# MCH_FPGA_Banks_64_65_HR.net
KiCad netlist of a schematic drawn in Altium Designer
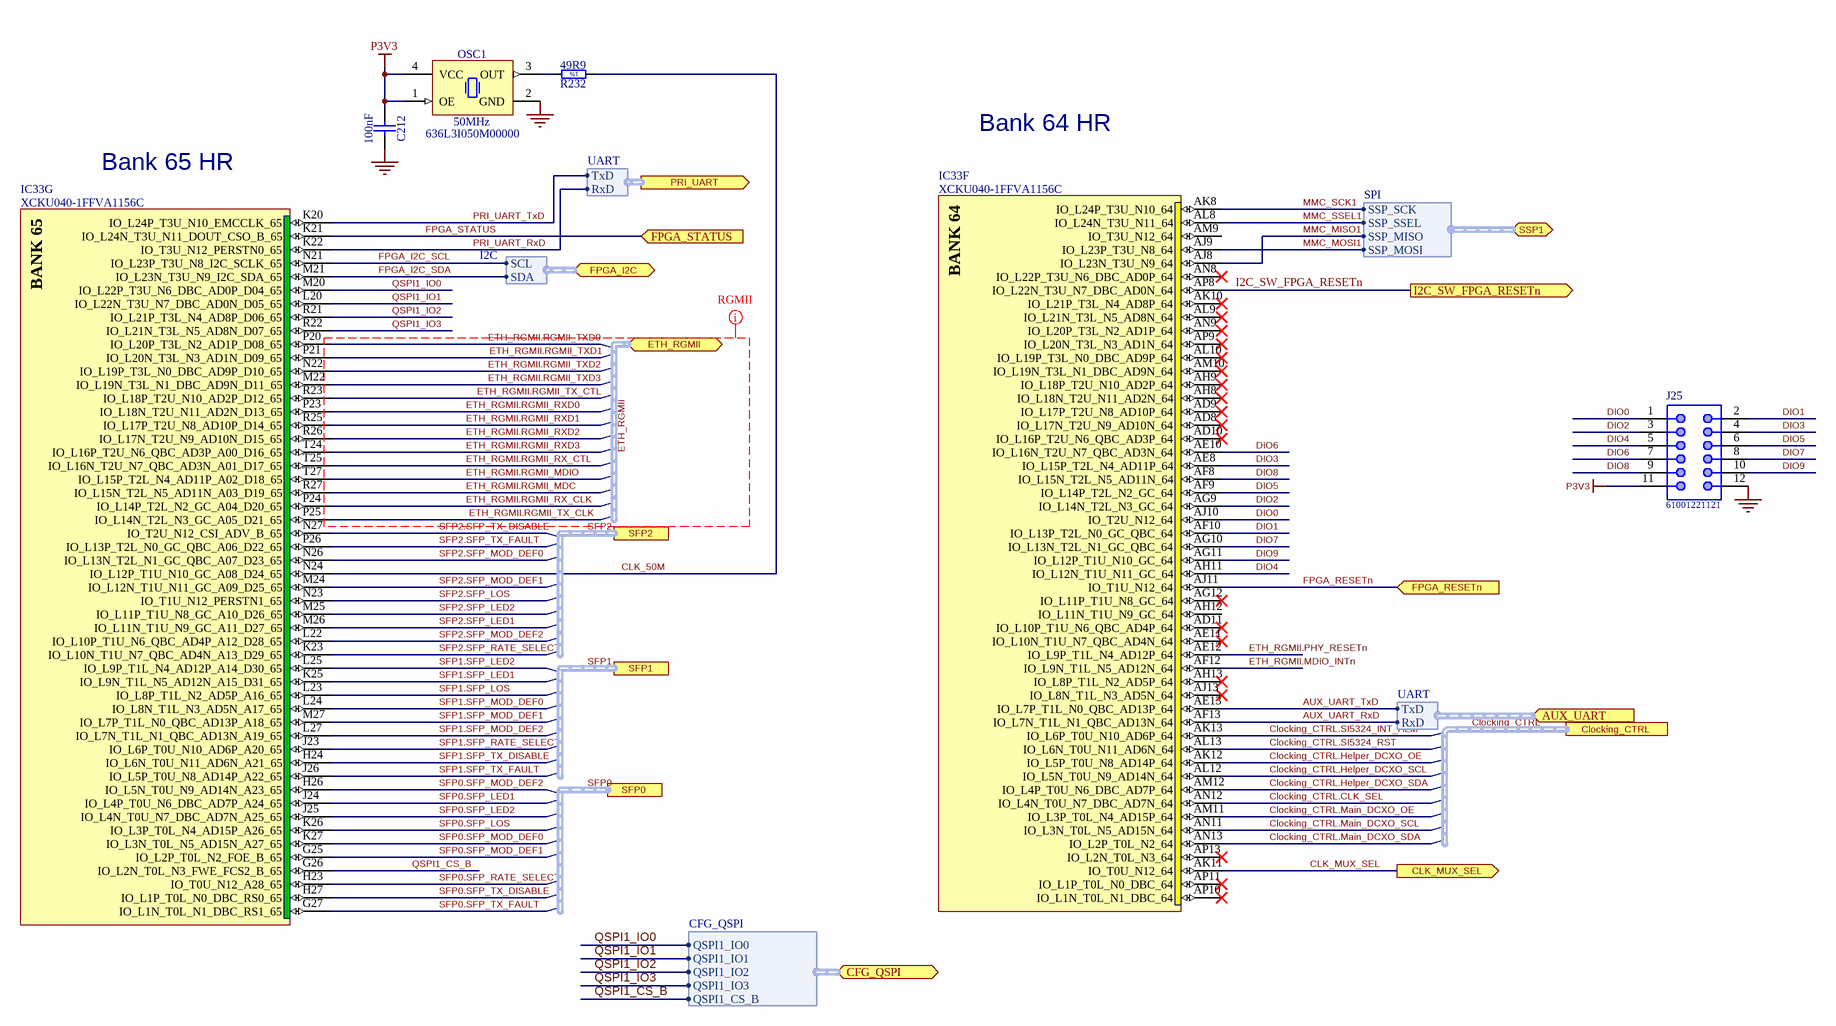
[diagram p0: MCH_FPGA_Banks_64_65_HR.SchDoc]

(export (version "E")
  (design (tool "Eeschema 10.0.6"))
  (components
    (comp (ref "C212")
      (value "100nF")
      (footprint "CAPC0603X33N")
      (description "Non-polarised capacitor")
      (fields
        (field (name "MANUFACTURER PART NUMBER") "CC0201_100NF_6.3V_10%_X5R")
        (field (name "MANUFACTURER") "GENERIC")
        (field (name "AUTHOR") "CERN DEM JLC")
      )
      (libsource (lib "Capacitors") (part "Capacitor - non polarized"))
    )
    (comp (ref "IC33")
      (value "XCKU040-1FFVA1156C")
      (footprint "BGA1156C100P34X34_3500X3500X350")
      (description "Kintex UltraScale FPGA, 520 I/O, 530K Cells, 1156-Ball BGA, Speed Grade 1, Commercial Grade")
      (fields (field (name "MANUFACTURER") "XILINX") (field (name "AUTHOR") "CERN DEM CA"))
      (libsource (lib "ICs And Semiconductors") (part "XCKU040-1FFVA1156C"))
    )
    (comp (ref "J25")
      (value "61001221121")
      (footprint "61001221121")
      (description "WR-PHD Pin Header, SMT, pitch 2.54mm, Dual Row, Vertical, 12p")
      (fields (field (name "MANUFACTURER") "Wurth Elektronik"))
      (libsource (lib "Altium_WR-PHD (rev20a)") (part "61001221121"))
    )
    (comp (ref "OSC1")
      (value "50MHz")
      (footprint "OSCSC254P320X500X130-4N")
      (description "Oscillator 4 pins 1=OE 2=GND 3=OUT 4=VCC")
      (fields
        (field (name "MANUFACTURER PART NUMBER") "636L3I050M00000")
        (field (name "MANUFACTURER") "CTS ELECTRONIC COMPONENTS")
        (field (name "PART NUMBER") "OSC_50MHZ_CTS_636L3I050M00000")
        (field (name "AUTHOR") "CERN DEM JMW")
      )
      (libsource (lib "ICs And Semiconductors") (part "Oscillator 1OE 2GND 3OUT 4VCC"))
    )
    (comp (ref "R232")
      (value "49R9")
      (footprint "RESC1005X40N")
      (description "Resistor - 1%")
      (fields
        (field (name "MANUFACTURER PART NUMBER") "R0402_49R9_1%_0.0625W_100PPM")
        (field (name "MANUFACTURER") "GENERIC")
        (field (name "AUTHOR") "CERN DEM JLC")
      )
      (libsource (lib "Resistors") (part "Resistor - 1%"))
    )
  )
  (nets
    (net (code "10") (name "/AUX_UART_RxD") (class "Default")
      (node (ref "IC33") (pin "AF13") (pinfunction "IO_L7N_T1L_N1_QBC_AD13N_64_AF13") (pintype "bidirectional"))
    )
    (net (code "11") (name "/AUX_UART_TxD") (class "Default")
      (node (ref "IC33") (pin "AE13") (pinfunction "IO_L7P_T1L_N0_QBC_AD13P_64_AE13") (pintype "bidirectional"))
    )
    (net (code "12") (name "/CLK_50M") (class "Default")
      (node (ref "IC33") (pin "N24") (pinfunction "IO_L12P_T1U_N10_GC_A08_D24_65_N24") (pintype "bidirectional"))
      (node (ref "R232") (pin "1") (pinfunction "1_1") (pintype "passive"))
    )
    (net (code "13") (name "/CLK_MUX_SEL") (class "Default")
      (node (ref "IC33") (pin "AK11") (pinfunction "IO_T0U_N12_64_AK11") (pintype "bidirectional"))
    )
    (net (code "14") (name "/Clocking_CTRL.CLK_SEL") (class "Default")
      (node (ref "IC33") (pin "AN12") (pinfunction "IO_L4N_T0U_N7_DBC_AD7N_64_AN12") (pintype "bidirectional"))
    )
    (net (code "15") (name "/Clocking_CTRL.Helper_DCXO_OE") (class "Default")
      (node (ref "IC33") (pin "AK12") (pinfunction "IO_L5P_T0U_N8_AD14P_64_AK12") (pintype "bidirectional"))
    )
    (net (code "16") (name "/Clocking_CTRL.Helper_DCXO_SCL") (class "Default")
      (node (ref "IC33") (pin "AL12") (pinfunction "IO_L5N_T0U_N9_AD14N_64_AL12") (pintype "bidirectional"))
    )
    (net (code "17") (name "/Clocking_CTRL.Helper_DCXO_SDA") (class "Default")
      (node (ref "IC33") (pin "AM12") (pinfunction "IO_L4P_T0U_N6_DBC_AD7P_64_AM12") (pintype "bidirectional"))
    )
    (net (code "18") (name "/Clocking_CTRL.Main_DCXO_OE") (class "Default")
      (node (ref "IC33") (pin "AM11") (pinfunction "IO_L3P_T0L_N4_AD15P_64_AM11") (pintype "bidirectional"))
    )
    (net (code "19") (name "/Clocking_CTRL.Main_DCXO_SCL") (class "Default")
      (node (ref "IC33") (pin "AN11") (pinfunction "IO_L3N_T0L_N5_AD15N_64_AN11") (pintype "bidirectional"))
    )
    (net (code "20") (name "/Clocking_CTRL.Main_DCXO_SDA") (class "Default")
      (node (ref "IC33") (pin "AN13") (pinfunction "IO_L2P_T0L_N2_64_AN13") (pintype "bidirectional"))
    )
    (net (code "21") (name "/Clocking_CTRL.SI5324_INT_ALM") (class "Default")
      (node (ref "IC33") (pin "AK13") (pinfunction "IO_L6P_T0U_N10_AD6P_64_AK13") (pintype "bidirectional"))
    )
    (net (code "22") (name "/Clocking_CTRL.SI5324_RST") (class "Default")
      (node (ref "IC33") (pin "AL13") (pinfunction "IO_L6N_T0U_N11_AD6N_64_AL13") (pintype "bidirectional"))
    )
    (net (code "23") (name "/DIO0") (class "Default")
      (node (ref "IC33") (pin "AJ10") (pinfunction "IO_T2U_N12_64_AJ10") (pintype "bidirectional"))
      (node (ref "J25") (pin "1") (pinfunction "1_1") (pintype "passive"))
    )
    (net (code "24") (name "/DIO1") (class "Default")
      (node (ref "IC33") (pin "AF10") (pinfunction "IO_L13P_T2L_N0_GC_QBC_64_AF10") (pintype "bidirectional"))
      (node (ref "J25") (pin "2") (pinfunction "2_2") (pintype "passive"))
    )
    (net (code "25") (name "/DIO2") (class "Default")
      (node (ref "IC33") (pin "AG9") (pinfunction "IO_L14N_T2L_N3_GC_64_AG9") (pintype "bidirectional"))
      (node (ref "J25") (pin "3") (pinfunction "3_3") (pintype "passive"))
    )
    (net (code "26") (name "/DIO3") (class "Default")
      (node (ref "IC33") (pin "AE8") (pinfunction "IO_L15P_T2L_N4_AD11P_64_AE8") (pintype "bidirectional"))
      (node (ref "J25") (pin "4") (pinfunction "4_4") (pintype "passive"))
    )
    (net (code "27") (name "/DIO4") (class "Default")
      (node (ref "IC33") (pin "AH11") (pinfunction "IO_L12N_T1U_N11_GC_64_AH11") (pintype "bidirectional"))
      (node (ref "J25") (pin "5") (pinfunction "5_5") (pintype "passive"))
    )
    (net (code "28") (name "/DIO5") (class "Default")
      (node (ref "IC33") (pin "AF9") (pinfunction "IO_L14P_T2L_N2_GC_64_AF9") (pintype "bidirectional"))
      (node (ref "J25") (pin "6") (pinfunction "6_6") (pintype "passive"))
    )
    (net (code "29") (name "/DIO6") (class "Default")
      (node (ref "IC33") (pin "AE10") (pinfunction "IO_L16N_T2U_N7_QBC_AD3N_64_AE10") (pintype "bidirectional"))
      (node (ref "J25") (pin "7") (pinfunction "7_7") (pintype "passive"))
    )
    (net (code "30") (name "/DIO7") (class "Default")
      (node (ref "IC33") (pin "AG10") (pinfunction "IO_L13N_T2L_N1_GC_QBC_64_AG10") (pintype "bidirectional"))
      (node (ref "J25") (pin "8") (pinfunction "8_8") (pintype "passive"))
    )
    (net (code "31") (name "/DIO8") (class "Default")
      (node (ref "IC33") (pin "AF8") (pinfunction "IO_L15N_T2L_N5_AD11N_64_AF8") (pintype "bidirectional"))
      (node (ref "J25") (pin "9") (pinfunction "9_9") (pintype "passive"))
    )
    (net (code "32") (name "/DIO9") (class "Default")
      (node (ref "IC33") (pin "AG11") (pinfunction "IO_L12P_T1U_N10_GC_64_AG11") (pintype "bidirectional"))
      (node (ref "J25") (pin "10") (pinfunction "10_10") (pintype "passive"))
    )
    (net (code "33") (name "/ETH_RGMII.MDIO_INTn") (class "Default")
      (node (ref "IC33") (pin "AF12") (pinfunction "IO_L9N_T1L_N5_AD12N_64_AF12") (pintype "bidirectional"))
    )
    (net (code "34") (name "/ETH_RGMII.PHY_RESETn") (class "Default")
      (node (ref "IC33") (pin "AE12") (pinfunction "IO_L9P_T1L_N4_AD12P_64_AE12") (pintype "bidirectional"))
    )
    (net (code "35") (name "/ETH_RGMII.RGMII_MDC") (class "Default")
      (node (ref "IC33") (pin "R27") (pinfunction "IO_L15N_T2L_N5_AD11N_A03_D19_65_R27") (pintype "bidirectional"))
    )
    (net (code "36") (name "/ETH_RGMII.RGMII_MDIO") (class "Default")
      (node (ref "IC33") (pin "T27") (pinfunction "IO_L15P_T2L_N4_AD11P_A02_D18_65_T27") (pintype "bidirectional"))
    )
    (net (code "37") (name "/ETH_RGMII.RGMII_RXD0") (class "Default")
      (node (ref "IC33") (pin "P23") (pinfunction "IO_L18N_T2U_N11_AD2N_D13_65_P23") (pintype "bidirectional"))
    )
    (net (code "38") (name "/ETH_RGMII.RGMII_RXD1") (class "Default")
      (node (ref "IC33") (pin "R25") (pinfunction "IO_L17P_T2U_N8_AD10P_D14_65_R25") (pintype "bidirectional"))
    )
    (net (code "39") (name "/ETH_RGMII.RGMII_RXD2") (class "Default")
      (node (ref "IC33") (pin "R26") (pinfunction "IO_L17N_T2U_N9_AD10N_D15_65_R26") (pintype "bidirectional"))
    )
    (net (code "40") (name "/ETH_RGMII.RGMII_RXD3") (class "Default")
      (node (ref "IC33") (pin "T24") (pinfunction "IO_L16P_T2U_N6_QBC_AD3P_A00_D16_65_T24") (pintype "bidirectional"))
    )
    (net (code "41") (name "/ETH_RGMII.RGMII_RX_CLK") (class "Default")
      (node (ref "IC33") (pin "P24") (pinfunction "IO_L14P_T2L_N2_GC_A04_D20_65_P24") (pintype "bidirectional"))
    )
    (net (code "42") (name "/ETH_RGMII.RGMII_RX_CTL") (class "Default")
      (node (ref "IC33") (pin "T25") (pinfunction "IO_L16N_T2U_N7_QBC_AD3N_A01_D17_65_T25") (pintype "bidirectional"))
    )
    (net (code "43") (name "/ETH_RGMII.RGMII_TXD0") (class "Default")
      (node (ref "IC33") (pin "P20") (pinfunction "IO_L20P_T3L_N2_AD1P_D08_65_P20") (pintype "bidirectional"))
    )
    (net (code "44") (name "/ETH_RGMII.RGMII_TXD1") (class "Default")
      (node (ref "IC33") (pin "P21") (pinfunction "IO_L20N_T3L_N3_AD1N_D09_65_P21") (pintype "bidirectional"))
    )
    (net (code "45") (name "/ETH_RGMII.RGMII_TXD2") (class "Default")
      (node (ref "IC33") (pin "N22") (pinfunction "IO_L19P_T3L_N0_DBC_AD9P_D10_65_N22") (pintype "bidirectional"))
    )
    (net (code "46") (name "/ETH_RGMII.RGMII_TXD3") (class "Default")
      (node (ref "IC33") (pin "M22") (pinfunction "IO_L19N_T3L_N1_DBC_AD9N_D11_65_M22") (pintype "bidirectional"))
    )
    (net (code "47") (name "/ETH_RGMII.RGMII_TX_CLK") (class "Default")
      (node (ref "IC33") (pin "P25") (pinfunction "IO_L14N_T2L_N3_GC_A05_D21_65_P25") (pintype "bidirectional"))
    )
    (net (code "48") (name "/ETH_RGMII.RGMII_TX_CTL") (class "Default")
      (node (ref "IC33") (pin "R23") (pinfunction "IO_L18P_T2U_N10_AD2P_D12_65_R23") (pintype "bidirectional"))
    )
    (net (code "49") (name "/FPGA_I2C_SCL") (class "Default")
      (node (ref "IC33") (pin "N21") (pinfunction "IO_L23P_T3U_N8_I2C_SCLK_65_N21") (pintype "bidirectional"))
    )
    (net (code "50") (name "/FPGA_I2C_SDA") (class "Default")
      (node (ref "IC33") (pin "M21") (pinfunction "IO_L23N_T3U_N9_I2C_SDA_65_M21") (pintype "bidirectional"))
    )
    (net (code "51") (name "/FPGA_RESETn") (class "Default")
      (node (ref "IC33") (pin "AJ11") (pinfunction "IO_T1U_N12_64_AJ11") (pintype "bidirectional"))
    )
    (net (code "52") (name "/FPGA_STATUS") (class "Default")
      (node (ref "IC33") (pin "K21") (pinfunction "IO_L24N_T3U_N11_DOUT_CSO_B_65_K21") (pintype "bidirectional"))
    )
    (net (code "53") (name "/I2C_SW_FPGA_RESETn") (class "Default")
      (node (ref "IC33") (pin "AP8") (pinfunction "IO_L22N_T3U_N7_DBC_AD0N_64_AP8") (pintype "bidirectional"))
    )
    (net (code "54") (name "/MMC_MISO1") (class "Default")
      (node (ref "IC33") (pin "AJ8") (pinfunction "IO_L23N_T3U_N9_64_AJ8") (pintype "bidirectional"))
    )
    (net (code "55") (name "/MMC_MOSI1") (class "Default")
      (node (ref "IC33") (pin "AJ9") (pinfunction "IO_L23P_T3U_N8_64_AJ9") (pintype "bidirectional"))
    )
    (net (code "56") (name "/MMC_SCK1") (class "Default")
      (node (ref "IC33") (pin "AK8") (pinfunction "IO_L24P_T3U_N10_64_AK8") (pintype "bidirectional"))
    )
    (net (code "57") (name "/MMC_SSEL1") (class "Default")
      (node (ref "IC33") (pin "AL8") (pinfunction "IO_L24N_T3U_N11_64_AL8") (pintype "bidirectional"))
    )
    (net (code "58") (name "/PRI_UART_RxD") (class "Default")
      (node (ref "IC33") (pin "K22") (pinfunction "IO_T3U_N12_PERSTN0_65_K22") (pintype "bidirectional"))
    )
    (net (code "59") (name "/PRI_UART_TxD") (class "Default")
      (node (ref "IC33") (pin "K20") (pinfunction "IO_L24P_T3U_N10_EMCCLK_65_K20") (pintype "bidirectional"))
    )
    (net (code "60") (name "/QSPI1_CS_B") (class "Default")
      (node (ref "IC33") (pin "G26") (pinfunction "IO_L2N_T0L_N3_FWE_FCS2_B_65_G26") (pintype "bidirectional"))
    )
    (net (code "61") (name "/QSPI1_IO0") (class "Default")
      (node (ref "IC33") (pin "M20") (pinfunction "IO_L22P_T3U_N6_DBC_AD0P_D04_65_M20") (pintype "bidirectional"))
    )
    (net (code "62") (name "/QSPI1_IO1") (class "Default")
      (node (ref "IC33") (pin "L20") (pinfunction "IO_L22N_T3U_N7_DBC_AD0N_D05_65_L20") (pintype "bidirectional"))
    )
    (net (code "63") (name "/QSPI1_IO2") (class "Default")
      (node (ref "IC33") (pin "R21") (pinfunction "IO_L21P_T3L_N4_AD8P_D06_65_R21") (pintype "bidirectional"))
    )
    (net (code "64") (name "/QSPI1_IO3") (class "Default")
      (node (ref "IC33") (pin "R22") (pinfunction "IO_L21N_T3L_N5_AD8N_D07_65_R22") (pintype "bidirectional"))
    )
    (net (code "65") (name "/SFP0.SFP_LED1") (class "Default")
      (node (ref "IC33") (pin "J24") (pinfunction "IO_L4P_T0U_N6_DBC_AD7P_A24_65_J24") (pintype "bidirectional"))
    )
    (net (code "66") (name "/SFP0.SFP_LED2") (class "Default")
      (node (ref "IC33") (pin "J25") (pinfunction "IO_L4N_T0U_N7_DBC_AD7N_A25_65_J25") (pintype "bidirectional"))
    )
    (net (code "67") (name "/SFP0.SFP_LOS") (class "Default")
      (node (ref "IC33") (pin "K26") (pinfunction "IO_L3P_T0L_N4_AD15P_A26_65_K26") (pintype "bidirectional"))
    )
    (net (code "68") (name "/SFP0.SFP_MOD_DEF0") (class "Default")
      (node (ref "IC33") (pin "K27") (pinfunction "IO_L3N_T0L_N5_AD15N_A27_65_K27") (pintype "bidirectional"))
    )
    (net (code "69") (name "/SFP0.SFP_MOD_DEF1") (class "Default")
      (node (ref "IC33") (pin "G25") (pinfunction "IO_L2P_T0L_N2_FOE_B_65_G25") (pintype "bidirectional"))
    )
    (net (code "70") (name "/SFP0.SFP_MOD_DEF2") (class "Default")
      (node (ref "IC33") (pin "H26") (pinfunction "IO_L5N_T0U_N9_AD14N_A23_65_H26") (pintype "bidirectional"))
    )
    (net (code "71") (name "/SFP0.SFP_RATE_SELECT") (class "Default")
      (node (ref "IC33") (pin "H23") (pinfunction "IO_T0U_N12_A28_65_H23") (pintype "bidirectional"))
    )
    (net (code "72") (name "/SFP0.SFP_TX_DISABLE") (class "Default")
      (node (ref "IC33") (pin "H27") (pinfunction "IO_L1P_T0L_N0_DBC_RS0_65_H27") (pintype "bidirectional"))
    )
    (net (code "73") (name "/SFP0.SFP_TX_FAULT") (class "Default")
      (node (ref "IC33") (pin "G27") (pinfunction "IO_L1N_T0L_N1_DBC_RS1_65_G27") (pintype "bidirectional"))
    )
    (net (code "74") (name "/SFP1.SFP_LED1") (class "Default")
      (node (ref "IC33") (pin "K25") (pinfunction "IO_L9N_T1L_N5_AD12N_A15_D31_65_K25") (pintype "bidirectional"))
    )
    (net (code "75") (name "/SFP1.SFP_LED2") (class "Default")
      (node (ref "IC33") (pin "L25") (pinfunction "IO_L9P_T1L_N4_AD12P_A14_D30_65_L25") (pintype "bidirectional"))
    )
    (net (code "76") (name "/SFP1.SFP_LOS") (class "Default")
      (node (ref "IC33") (pin "L23") (pinfunction "IO_L8P_T1L_N2_AD5P_A16_65_L23") (pintype "bidirectional"))
    )
    (net (code "77") (name "/SFP1.SFP_MOD_DEF0") (class "Default")
      (node (ref "IC33") (pin "L24") (pinfunction "IO_L8N_T1L_N3_AD5N_A17_65_L24") (pintype "bidirectional"))
    )
    (net (code "78") (name "/SFP1.SFP_MOD_DEF1") (class "Default")
      (node (ref "IC33") (pin "M27") (pinfunction "IO_L7P_T1L_N0_QBC_AD13P_A18_65_M27") (pintype "bidirectional"))
    )
    (net (code "79") (name "/SFP1.SFP_MOD_DEF2") (class "Default")
      (node (ref "IC33") (pin "L27") (pinfunction "IO_L7N_T1L_N1_QBC_AD13N_A19_65_L27") (pintype "bidirectional"))
    )
    (net (code "80") (name "/SFP1.SFP_RATE_SELECT") (class "Default")
      (node (ref "IC33") (pin "J23") (pinfunction "IO_L6P_T0U_N10_AD6P_A20_65_J23") (pintype "bidirectional"))
    )
    (net (code "81") (name "/SFP1.SFP_TX_DISABLE") (class "Default")
      (node (ref "IC33") (pin "H24") (pinfunction "IO_L6N_T0U_N11_AD6N_A21_65_H24") (pintype "bidirectional"))
    )
    (net (code "82") (name "/SFP1.SFP_TX_FAULT") (class "Default")
      (node (ref "IC33") (pin "J26") (pinfunction "IO_L5P_T0U_N8_AD14P_A22_65_J26") (pintype "bidirectional"))
    )
    (net (code "83") (name "/SFP2.SFP_LED1") (class "Default")
      (node (ref "IC33") (pin "M26") (pinfunction "IO_L11N_T1U_N9_GC_A11_D27_65_M26") (pintype "bidirectional"))
    )
    (net (code "84") (name "/SFP2.SFP_LED2") (class "Default")
      (node (ref "IC33") (pin "M25") (pinfunction "IO_L11P_T1U_N8_GC_A10_D26_65_M25") (pintype "bidirectional"))
    )
    (net (code "85") (name "/SFP2.SFP_LOS") (class "Default")
      (node (ref "IC33") (pin "N23") (pinfunction "IO_T1U_N12_PERSTN1_65_N23") (pintype "bidirectional"))
    )
    (net (code "86") (name "/SFP2.SFP_MOD_DEF0") (class "Default")
      (node (ref "IC33") (pin "N26") (pinfunction "IO_L13N_T2L_N1_GC_QBC_A07_D23_65_N26") (pintype "bidirectional"))
    )
    (net (code "87") (name "/SFP2.SFP_MOD_DEF1") (class "Default")
      (node (ref "IC33") (pin "M24") (pinfunction "IO_L12N_T1U_N11_GC_A09_D25_65_M24") (pintype "bidirectional"))
    )
    (net (code "88") (name "/SFP2.SFP_MOD_DEF2") (class "Default")
      (node (ref "IC33") (pin "L22") (pinfunction "IO_L10P_T1U_N6_QBC_AD4P_A12_D28_65_L22") (pintype "bidirectional"))
    )
    (net (code "89") (name "/SFP2.SFP_RATE_SELECT") (class "Default")
      (node (ref "IC33") (pin "K23") (pinfunction "IO_L10N_T1U_N7_QBC_AD4N_A13_D29_65_K23") (pintype "bidirectional"))
    )
    (net (code "90") (name "/SFP2.SFP_TX_DISABLE") (class "Default")
      (node (ref "IC33") (pin "N27") (pinfunction "IO_T2U_N12_CSI_ADV_B_65_N27") (pintype "bidirectional"))
    )
    (net (code "91") (name "/SFP2.SFP_TX_FAULT") (class "Default")
      (node (ref "IC33") (pin "P26") (pinfunction "IO_L13P_T2L_N0_GC_QBC_A06_D22_65_P26") (pintype "bidirectional"))
    )
    (net (code "101") (name "GND") (class "Default")
      (node (ref "C212") (pin "1") (pinfunction "1_1") (pintype "passive"))
      (node (ref "J25") (pin "12") (pinfunction "12_12") (pintype "passive"))
      (node (ref "OSC1") (pin "2") (pinfunction "GND_2") (pintype "power_in"))
    )
    (net (code "102") (name "Net-(OSC1-OUT)") (class "Default")
      (node (ref "OSC1") (pin "3") (pinfunction "OUT_3") (pintype "output"))
      (node (ref "R232") (pin "2") (pinfunction "2_2") (pintype "passive"))
    )
    (net (code "103") (name "P3V3") (class "Default")
      (node (ref "C212") (pin "2") (pinfunction "2_2") (pintype "passive"))
      (node (ref "J25") (pin "11") (pinfunction "11_11") (pintype "passive"))
      (node (ref "OSC1") (pin "1") (pinfunction "OE_1") (pintype "input"))
      (node (ref "OSC1") (pin "4") (pinfunction "VCC_4") (pintype "power_in"))
    )
    (net (code "104") (name "unconnected-(IC33F-IO_L1N_T0L_N1_DBC_64-PadAP10)") (class "Default")
      (node (ref "IC33") (pin "AP10") (pinfunction "IO_L1N_T0L_N1_DBC_64_AP10") (pintype "bidirectional+no_connect"))
    )
    (net (code "105") (name "unconnected-(IC33F-IO_L1P_T0L_N0_DBC_64-PadAP11)") (class "Default")
      (node (ref "IC33") (pin "AP11") (pinfunction "IO_L1P_T0L_N0_DBC_64_AP11") (pintype "bidirectional+no_connect"))
    )
    (net (code "106") (name "unconnected-(IC33F-IO_L2N_T0L_N3_64-PadAP13)") (class "Default")
      (node (ref "IC33") (pin "AP13") (pinfunction "IO_L2N_T0L_N3_64_AP13") (pintype "bidirectional+no_connect"))
    )
    (net (code "107") (name "unconnected-(IC33F-IO_L8N_T1L_N3_AD5N_64-PadAJ13)") (class "Default")
      (node (ref "IC33") (pin "AJ13") (pinfunction "IO_L8N_T1L_N3_AD5N_64_AJ13") (pintype "bidirectional+no_connect"))
    )
    (net (code "108") (name "unconnected-(IC33F-IO_L8P_T1L_N2_AD5P_64-PadAH13)") (class "Default")
      (node (ref "IC33") (pin "AH13") (pinfunction "IO_L8P_T1L_N2_AD5P_64_AH13") (pintype "bidirectional+no_connect"))
    )
    (net (code "109") (name "unconnected-(IC33F-IO_L10N_T1U_N7_QBC_AD4N_64-PadAE11)") (class "Default")
      (node (ref "IC33") (pin "AE11") (pinfunction "IO_L10N_T1U_N7_QBC_AD4N_64_AE11") (pintype "bidirectional+no_connect"))
    )
    (net (code "110") (name "unconnected-(IC33F-IO_L10P_T1U_N6_QBC_AD4P_64-PadAD11)") (class "Default")
      (node (ref "IC33") (pin "AD11") (pinfunction "IO_L10P_T1U_N6_QBC_AD4P_64_AD11") (pintype "bidirectional+no_connect"))
    )
    (net (code "111") (name "unconnected-(IC33F-IO_L11N_T1U_N9_GC_64-PadAH12)") (class "Default")
      (node (ref "IC33") (pin "AH12") (pinfunction "IO_L11N_T1U_N9_GC_64_AH12") (pintype "bidirectional"))
    )
    (net (code "112") (name "unconnected-(IC33F-IO_L11P_T1U_N8_GC_64-PadAG12)") (class "Default")
      (node (ref "IC33") (pin "AG12") (pinfunction "IO_L11P_T1U_N8_GC_64_AG12") (pintype "bidirectional+no_connect"))
    )
    (net (code "113") (name "unconnected-(IC33F-IO_L16P_T2U_N6_QBC_AD3P_64-PadAD10)") (class "Default")
      (node (ref "IC33") (pin "AD10") (pinfunction "IO_L16P_T2U_N6_QBC_AD3P_64_AD10") (pintype "bidirectional+no_connect"))
    )
    (net (code "114") (name "unconnected-(IC33F-IO_L17N_T2U_N9_AD10N_64-PadAD8)") (class "Default")
      (node (ref "IC33") (pin "AD8") (pinfunction "IO_L17N_T2U_N9_AD10N_64_AD8") (pintype "bidirectional+no_connect"))
    )
    (net (code "115") (name "unconnected-(IC33F-IO_L17P_T2U_N8_AD10P_64-PadAD9)") (class "Default")
      (node (ref "IC33") (pin "AD9") (pinfunction "IO_L17P_T2U_N8_AD10P_64_AD9") (pintype "bidirectional+no_connect"))
    )
    (net (code "116") (name "unconnected-(IC33F-IO_L18N_T2U_N11_AD2N_64-PadAH8)") (class "Default")
      (node (ref "IC33") (pin "AH8") (pinfunction "IO_L18N_T2U_N11_AD2N_64_AH8") (pintype "bidirectional+no_connect"))
    )
    (net (code "117") (name "unconnected-(IC33F-IO_L18P_T2U_N10_AD2P_64-PadAH9)") (class "Default")
      (node (ref "IC33") (pin "AH9") (pinfunction "IO_L18P_T2U_N10_AD2P_64_AH9") (pintype "bidirectional+no_connect"))
    )
    (net (code "118") (name "unconnected-(IC33F-IO_L19N_T3L_N1_DBC_AD9N_64-PadAM10)") (class "Default")
      (node (ref "IC33") (pin "AM10") (pinfunction "IO_L19N_T3L_N1_DBC_AD9N_64_AM10") (pintype "bidirectional+no_connect"))
    )
    (net (code "119") (name "unconnected-(IC33F-IO_L19P_T3L_N0_DBC_AD9P_64-PadAL10)") (class "Default")
      (node (ref "IC33") (pin "AL10") (pinfunction "IO_L19P_T3L_N0_DBC_AD9P_64_AL10") (pintype "bidirectional+no_connect"))
    )
    (net (code "120") (name "unconnected-(IC33F-IO_L20N_T3L_N3_AD1N_64-PadAP9)") (class "Default")
      (node (ref "IC33") (pin "AP9") (pinfunction "IO_L20N_T3L_N3_AD1N_64_AP9") (pintype "bidirectional+no_connect"))
    )
    (net (code "121") (name "unconnected-(IC33F-IO_L20P_T3L_N2_AD1P_64-PadAN9)") (class "Default")
      (node (ref "IC33") (pin "AN9") (pinfunction "IO_L20P_T3L_N2_AD1P_64_AN9") (pintype "bidirectional+no_connect"))
    )
    (net (code "122") (name "unconnected-(IC33F-IO_L21N_T3L_N5_AD8N_64-PadAL9)") (class "Default")
      (node (ref "IC33") (pin "AL9") (pinfunction "IO_L21N_T3L_N5_AD8N_64_AL9") (pintype "bidirectional+no_connect"))
    )
    (net (code "123") (name "unconnected-(IC33F-IO_L21P_T3L_N4_AD8P_64-PadAK10)") (class "Default")
      (node (ref "IC33") (pin "AK10") (pinfunction "IO_L21P_T3L_N4_AD8P_64_AK10") (pintype "bidirectional+no_connect"))
    )
    (net (code "124") (name "unconnected-(IC33F-IO_L22P_T3U_N6_DBC_AD0P_64-PadAN8)") (class "Default")
      (node (ref "IC33") (pin "AN8") (pinfunction "IO_L22P_T3U_N6_DBC_AD0P_64_AN8") (pintype "bidirectional+no_connect"))
    )
    (net (code "125") (name "unconnected-(IC33F-IO_T3U_N12_64-PadAM9)") (class "Default")
      (node (ref "IC33") (pin "AM9") (pinfunction "IO_T3U_N12_64_AM9") (pintype "bidirectional"))
    )
  )
)
